# Motor_Driver_Schematic.net
KiCad netlist of a schematic drawn in Altium Designer
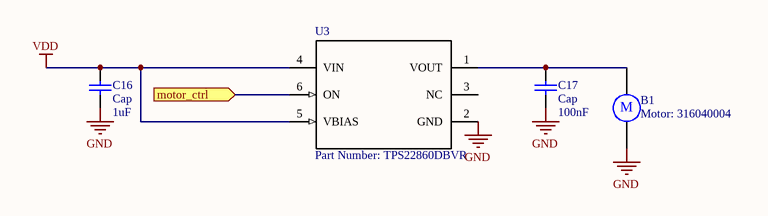
[diagram p0: Motor_Driver_Schematic.SchDoc]

(export (version "E")
  (design (tool "Eeschema 10.0.6"))
  (components
    (comp (ref "B1")
      (value "Motor: 316040004")
      (footprint "RB5-10.5")
      (description "Motor, General Kind")
      (fields (field (name "PUBLISHER") "Altium Limited"))
      (libsource (lib "Miscellaneous Devices") (part "Motor"))
    )
    (comp (ref "C16")
      (value "Cap")
      (footprint "C0805")
      (description "Capacitor")
      (fields (field (name "ALTIUM_VALUE") "1uF") (field (name "PUBLISHER") "Altium Limited"))
      (libsource (lib "Miscellaneous Devices") (part "Cap"))
    )
    (comp (ref "C17")
      (value "Cap")
      (footprint "C0805")
      (description "Capacitor")
      (fields (field (name "ALTIUM_VALUE") "100nF") (field (name "PUBLISHER") "Altium Limited"))
      (libsource (lib "Miscellaneous Devices") (part "Cap"))
    )
    (comp (ref "U3")
      (value "Part Number: TPS22860DBVR")
      (footprint "DBV0006A_N")
      (description "No Description Available")
      (fields
        (field (name "MANUFACTURER_PART_NUMBER") "TPS22860DBVR")
        (field (name "MANUFACTURER") "Texas Instruments")
        (field (name "COPYRIGHT") "Copyright (C) 2018 Accelerated Designs. All rights reserved")
      )
      (libsource (lib "TI-TPS22860DBVR") (part "TPS22860DBVR"))
    )
  )
  (nets
    (net (code "1") (name "/motor_ctrl") (class "Default")
      (node (ref "U3") (pin "6") (pinfunction "ON_6") (pintype "input"))
    )
    (net (code "2") (name "GND") (class "Default")
      (node (ref "B1") (pin "2") (pinfunction "2_2") (pintype "passive"))
      (node (ref "C16") (pin "1") (pinfunction "1_1") (pintype "passive"))
      (node (ref "C17") (pin "1") (pinfunction "1_1") (pintype "passive"))
      (node (ref "U3") (pin "2") (pinfunction "GND_2") (pintype "power_in"))
    )
    (net (code "3") (name "Net-(U3-VOUT)") (class "Default")
      (node (ref "B1") (pin "1") (pinfunction "1_1") (pintype "passive"))
      (node (ref "C17") (pin "2") (pinfunction "2_2") (pintype "passive"))
      (node (ref "U3") (pin "1") (pinfunction "VOUT_1") (pintype "power_in"))
    )
    (net (code "4") (name "VDD") (class "Default")
      (node (ref "C16") (pin "2") (pinfunction "2_2") (pintype "passive"))
      (node (ref "U3") (pin "4") (pinfunction "VIN_4") (pintype "power_in"))
      (node (ref "U3") (pin "5") (pinfunction "VBIAS_5") (pintype "input"))
    )
    (net (code "5") (name "unconnected-(U3-NC-Pad3)") (class "Default")
      (node (ref "U3") (pin "3") (pinfunction "NC_3") (pintype "passive"))
    )
  )
)
